# peldaszamlalo.net
KiCad netlist of a schematic drawn in EAGLE
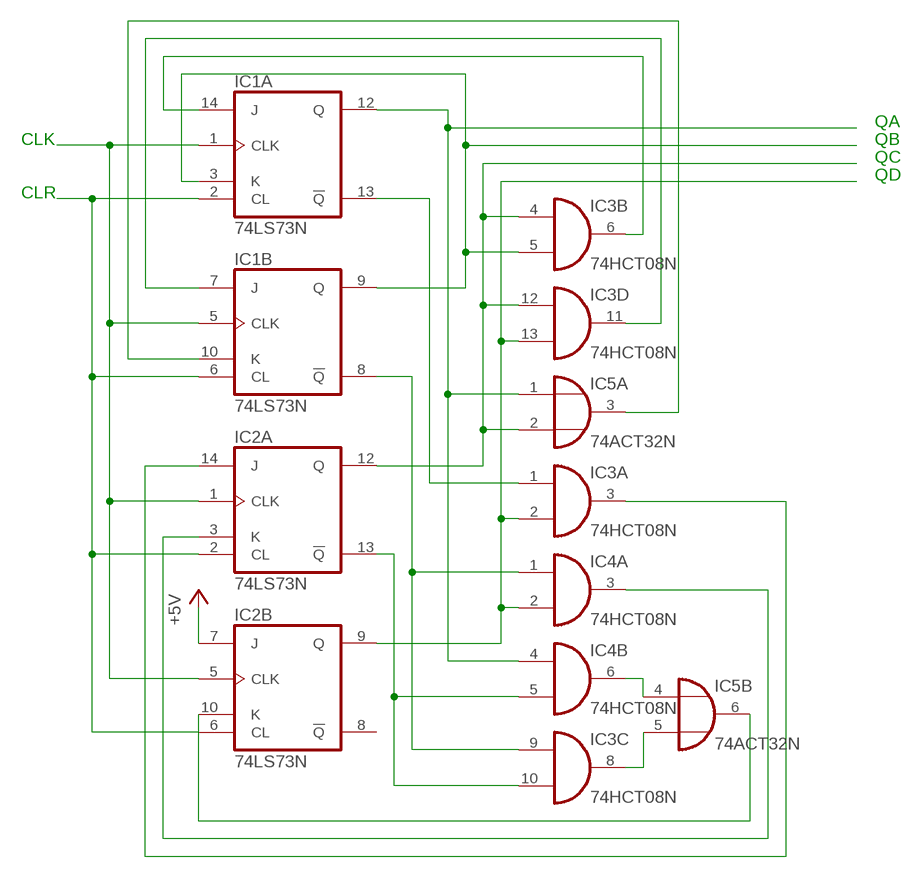
[diagram p0: schematic, sheet 1]

(export (version "E")
  (design (tool "Eeschema 10.0.6"))
  (components
    (comp (ref "IC1")
      (value "74LS73N")
      (footprint "eagle-import:DIL14")
      (libsource (lib "eagle-import") (part "7473NLS"))
    )
    (comp (ref "IC2")
      (value "74LS73N")
      (footprint "eagle-import:DIL14")
      (libsource (lib "eagle-import") (part "7473NLS"))
    )
    (comp (ref "IC3")
      (value "74HCT08N")
      (footprint "eagle-import:DIL14")
      (libsource (lib "eagle-import") (part "7408NHCT"))
    )
    (comp (ref "IC4")
      (value "74HCT08N")
      (footprint "eagle-import:DIL14")
      (libsource (lib "eagle-import") (part "7408NHCT"))
    )
    (comp (ref "IC5")
      (value "74ACT32N")
      (footprint "eagle-import:DIL14")
      (libsource (lib "eagle-import") (part "7432NACT"))
    )
  )
  (nets
    (net (code "1") (name "+5V") (class "Default")
      (node (ref "IC2") (pin "7") (pinfunction "J_7") (pintype "input"))
    )
    (net (code "2") (name "Net-(IC1A-CL)") (class "Default")
      (node (ref "IC1") (pin "2") (pinfunction "CL_2") (pintype "input"))
      (node (ref "IC1") (pin "6") (pinfunction "CL_6") (pintype "input"))
      (node (ref "IC2") (pin "2") (pinfunction "CL_2") (pintype "input"))
      (node (ref "IC2") (pin "6") (pinfunction "CL_6") (pintype "input"))
    )
    (net (code "3") (name "Net-(IC1A-CLK)") (class "Default")
      (node (ref "IC1") (pin "1") (pinfunction "CLK_1") (pintype "input"))
      (node (ref "IC1") (pin "5") (pinfunction "CLK_5") (pintype "input"))
      (node (ref "IC2") (pin "1") (pinfunction "CLK_1") (pintype "input"))
      (node (ref "IC2") (pin "5") (pinfunction "CLK_5") (pintype "input"))
    )
    (net (code "4") (name "Net-(IC1A-J)") (class "Default")
      (node (ref "IC1") (pin "14") (pinfunction "J_14") (pintype "input"))
      (node (ref "IC3") (pin "6") (pinfunction "O_6") (pintype "output"))
    )
    (net (code "5") (name "Net-(IC1A-K)") (class "Default")
      (node (ref "IC1") (pin "3") (pinfunction "K_3") (pintype "input"))
      (node (ref "IC1") (pin "9") (pinfunction "Q_9") (pintype "output"))
      (node (ref "IC3") (pin "5") (pinfunction "I1_5") (pintype "input"))
    )
    (net (code "6") (name "Net-(IC1A-Q)") (class "Default")
      (node (ref "IC1") (pin "12") (pinfunction "Q_12") (pintype "output"))
      (node (ref "IC4") (pin "4") (pinfunction "I0_4") (pintype "input"))
      (node (ref "IC5") (pin "1") (pinfunction "I0_1") (pintype "input"))
    )
    (net (code "7") (name "Net-(IC1A-~{Q})") (class "Default")
      (node (ref "IC1") (pin "13") (pinfunction "~{Q}_13") (pintype "output"))
      (node (ref "IC3") (pin "1") (pinfunction "I0_1") (pintype "input"))
    )
    (net (code "8") (name "Net-(IC1B-J)") (class "Default")
      (node (ref "IC1") (pin "7") (pinfunction "J_7") (pintype "input"))
      (node (ref "IC3") (pin "11") (pinfunction "O_11") (pintype "output"))
    )
    (net (code "9") (name "Net-(IC1B-K)") (class "Default")
      (node (ref "IC1") (pin "10") (pinfunction "K_10") (pintype "input"))
      (node (ref "IC5") (pin "3") (pinfunction "O_3") (pintype "output"))
    )
    (net (code "10") (name "Net-(IC1B-~{Q})") (class "Default")
      (node (ref "IC1") (pin "8") (pinfunction "~{Q}_8") (pintype "output"))
      (node (ref "IC3") (pin "9") (pinfunction "I0_9") (pintype "input"))
      (node (ref "IC4") (pin "1") (pinfunction "I0_1") (pintype "input"))
    )
    (net (code "11") (name "Net-(IC2A-J)") (class "Default")
      (node (ref "IC2") (pin "14") (pinfunction "J_14") (pintype "input"))
      (node (ref "IC3") (pin "3") (pinfunction "O_3") (pintype "output"))
    )
    (net (code "12") (name "Net-(IC2A-K)") (class "Default")
      (node (ref "IC2") (pin "3") (pinfunction "K_3") (pintype "input"))
      (node (ref "IC4") (pin "3") (pinfunction "O_3") (pintype "output"))
    )
    (net (code "13") (name "Net-(IC2A-Q)") (class "Default")
      (node (ref "IC2") (pin "12") (pinfunction "Q_12") (pintype "output"))
      (node (ref "IC3") (pin "12") (pinfunction "I0_12") (pintype "input"))
      (node (ref "IC3") (pin "4") (pinfunction "I0_4") (pintype "input"))
      (node (ref "IC5") (pin "2") (pinfunction "I1_2") (pintype "input"))
    )
    (net (code "14") (name "Net-(IC2A-~{Q})") (class "Default")
      (node (ref "IC2") (pin "13") (pinfunction "~{Q}_13") (pintype "output"))
      (node (ref "IC3") (pin "10") (pinfunction "I1_10") (pintype "input"))
      (node (ref "IC4") (pin "5") (pinfunction "I1_5") (pintype "input"))
    )
    (net (code "15") (name "Net-(IC2B-K)") (class "Default")
      (node (ref "IC2") (pin "10") (pinfunction "K_10") (pintype "input"))
      (node (ref "IC5") (pin "6") (pinfunction "O_6") (pintype "output"))
    )
    (net (code "16") (name "Net-(IC2B-Q)") (class "Default")
      (node (ref "IC2") (pin "9") (pinfunction "Q_9") (pintype "output"))
      (node (ref "IC3") (pin "13") (pinfunction "I1_13") (pintype "input"))
      (node (ref "IC3") (pin "2") (pinfunction "I1_2") (pintype "input"))
      (node (ref "IC4") (pin "2") (pinfunction "I1_2") (pintype "input"))
    )
    (net (code "17") (name "Net-(IC3C-O)") (class "Default")
      (node (ref "IC3") (pin "8") (pinfunction "O_8") (pintype "output"))
      (node (ref "IC5") (pin "5") (pinfunction "I1_5") (pintype "input"))
    )
    (net (code "18") (name "Net-(IC4B-O)") (class "Default")
      (node (ref "IC4") (pin "6") (pinfunction "O_6") (pintype "output"))
      (node (ref "IC5") (pin "4") (pinfunction "I0_4") (pintype "input"))
    )
    (net (code "19") (name "unconnected-(IC2B-~{Q}-Pad8)") (class "Default")
      (node (ref "IC2") (pin "8") (pinfunction "~{Q}_8") (pintype "output"))
    )
  )
)
